# Lighting.net
KiCad netlist of a schematic drawn in Altium Designer
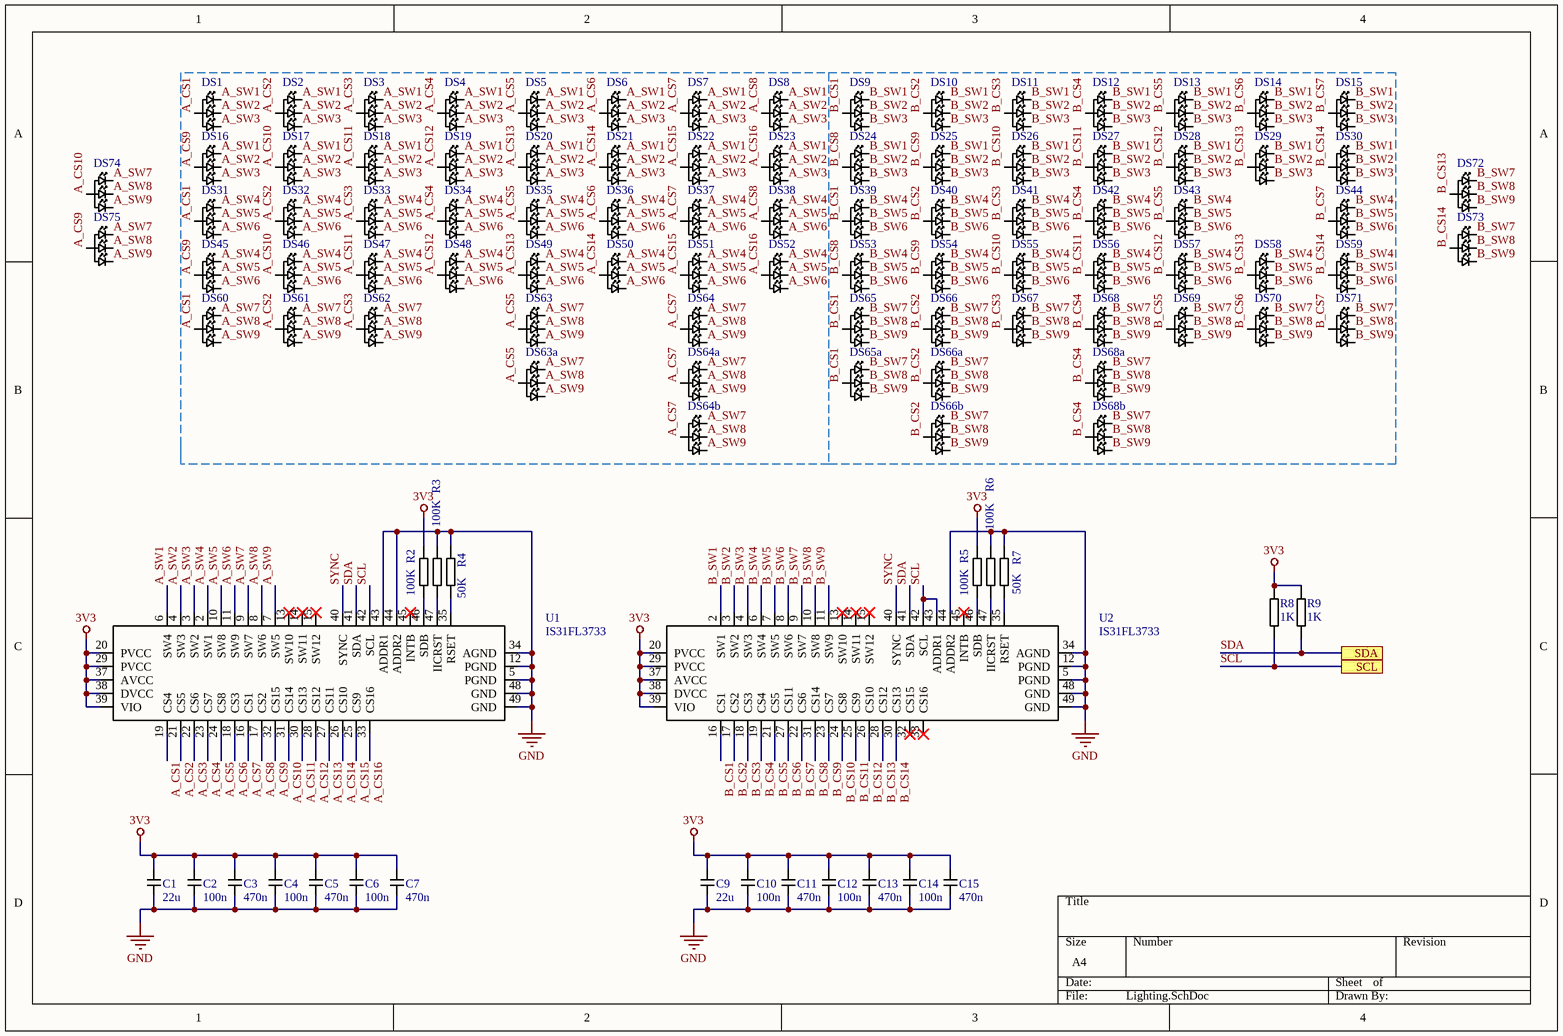
[diagram p0: Lighting.SchDoc]

(export (version "E")
  (design (tool "Eeschema 10.0.6"))
  (components
    (comp (ref "C1")
      (value "22u")
      (footprint "Capacitor_0603")
      (libsource (lib "NautilusKB") (part "Capacitor"))
    )
    (comp (ref "C2")
      (value "100n")
      (footprint "Capacitor_0603")
      (libsource (lib "NautilusKB") (part "Capacitor"))
    )
    (comp (ref "C3")
      (value "470n")
      (footprint "Capacitor_0603")
      (libsource (lib "NautilusKB") (part "Capacitor"))
    )
    (comp (ref "C4")
      (value "100n")
      (footprint "Capacitor_0603")
      (libsource (lib "NautilusKB") (part "Capacitor"))
    )
    (comp (ref "C5")
      (value "470n")
      (footprint "Capacitor_0603")
      (libsource (lib "NautilusKB") (part "Capacitor"))
    )
    (comp (ref "C6")
      (value "100n")
      (footprint "Capacitor_0603")
      (libsource (lib "NautilusKB") (part "Capacitor"))
    )
    (comp (ref "C7")
      (value "470n")
      (footprint "Capacitor_0603")
      (libsource (lib "NautilusKB") (part "Capacitor"))
    )
    (comp (ref "C9")
      (value "22u")
      (footprint "Capacitor_0603")
      (libsource (lib "NautilusKB") (part "Capacitor"))
    )
    (comp (ref "C10")
      (value "100n")
      (footprint "Capacitor_0603")
      (libsource (lib "NautilusKB") (part "Capacitor"))
    )
    (comp (ref "C11")
      (value "470n")
      (footprint "Capacitor_0603")
      (libsource (lib "NautilusKB") (part "Capacitor"))
    )
    (comp (ref "C12")
      (value "100n")
      (footprint "Capacitor_0603")
      (libsource (lib "NautilusKB") (part "Capacitor"))
    )
    (comp (ref "C13")
      (value "470n")
      (footprint "Capacitor_0603")
      (libsource (lib "NautilusKB") (part "Capacitor"))
    )
    (comp (ref "C14")
      (value "100n")
      (footprint "Capacitor_0603")
      (libsource (lib "NautilusKB") (part "Capacitor"))
    )
    (comp (ref "C15")
      (value "470n")
      (footprint "Capacitor_0603")
      (libsource (lib "NautilusKB") (part "Capacitor"))
    )
    (comp (ref "DS1")
      (value "RGB_CA")
      (footprint "LED_1616_4P")
      (libsource (lib "NautilusKB") (part "RGB_CA"))
    )
    (comp (ref "DS2")
      (value "RGB_CA")
      (footprint "LED_1616_4P")
      (libsource (lib "NautilusKB") (part "RGB_CA"))
    )
    (comp (ref "DS3")
      (value "RGB_CA")
      (footprint "LED_1616_4P")
      (libsource (lib "NautilusKB") (part "RGB_CA"))
    )
    (comp (ref "DS4")
      (value "RGB_CA")
      (footprint "LED_1616_4P")
      (libsource (lib "NautilusKB") (part "RGB_CA"))
    )
    (comp (ref "DS5")
      (value "RGB_CA")
      (footprint "LED_1616_4P")
      (libsource (lib "NautilusKB") (part "RGB_CA"))
    )
    (comp (ref "DS6")
      (value "RGB_CA")
      (footprint "LED_1616_4P")
      (libsource (lib "NautilusKB") (part "RGB_CA"))
    )
    (comp (ref "DS7")
      (value "RGB_CA")
      (footprint "LED_1616_4P")
      (libsource (lib "NautilusKB") (part "RGB_CA"))
    )
    (comp (ref "DS8")
      (value "RGB_CA")
      (footprint "LED_1616_4P")
      (libsource (lib "NautilusKB") (part "RGB_CA"))
    )
    (comp (ref "DS9")
      (value "RGB_CA")
      (footprint "LED_1616_4P")
      (libsource (lib "NautilusKB") (part "RGB_CA"))
    )
    (comp (ref "DS10")
      (value "RGB_CA")
      (footprint "LED_1616_4P")
      (libsource (lib "NautilusKB") (part "RGB_CA"))
    )
    (comp (ref "DS11")
      (value "RGB_CA")
      (footprint "LED_1616_4P")
      (libsource (lib "NautilusKB") (part "RGB_CA"))
    )
    (comp (ref "DS12")
      (value "RGB_CA")
      (footprint "LED_1616_4P")
      (libsource (lib "NautilusKB") (part "RGB_CA"))
    )
    (comp (ref "DS13")
      (value "RGB_CA")
      (footprint "LED_1616_4P")
      (libsource (lib "NautilusKB") (part "RGB_CA"))
    )
    (comp (ref "DS14")
      (value "RGB_CA")
      (footprint "LED_1616_4P")
      (libsource (lib "NautilusKB") (part "RGB_CA"))
    )
    (comp (ref "DS15")
      (value "RGB_CA")
      (footprint "LED_1616_4P")
      (libsource (lib "NautilusKB") (part "RGB_CA"))
    )
    (comp (ref "DS16")
      (value "RGB_CA")
      (footprint "LED_1616_4P")
      (libsource (lib "NautilusKB") (part "RGB_CA"))
    )
    (comp (ref "DS17")
      (value "RGB_CA")
      (footprint "LED_1616_4P")
      (libsource (lib "NautilusKB") (part "RGB_CA"))
    )
    (comp (ref "DS18")
      (value "RGB_CA")
      (footprint "LED_1616_4P")
      (libsource (lib "NautilusKB") (part "RGB_CA"))
    )
    (comp (ref "DS19")
      (value "RGB_CA")
      (footprint "LED_1616_4P")
      (libsource (lib "NautilusKB") (part "RGB_CA"))
    )
    (comp (ref "DS20")
      (value "RGB_CA")
      (footprint "LED_1616_4P")
      (libsource (lib "NautilusKB") (part "RGB_CA"))
    )
    (comp (ref "DS21")
      (value "RGB_CA")
      (footprint "LED_1616_4P")
      (libsource (lib "NautilusKB") (part "RGB_CA"))
    )
    (comp (ref "DS22")
      (value "RGB_CA")
      (footprint "LED_1616_4P")
      (libsource (lib "NautilusKB") (part "RGB_CA"))
    )
    (comp (ref "DS23")
      (value "RGB_CA")
      (footprint "LED_1616_4P")
      (libsource (lib "NautilusKB") (part "RGB_CA"))
    )
    (comp (ref "DS24")
      (value "RGB_CA")
      (footprint "LED_1616_4P")
      (libsource (lib "NautilusKB") (part "RGB_CA"))
    )
    (comp (ref "DS25")
      (value "RGB_CA")
      (footprint "LED_1616_4P")
      (libsource (lib "NautilusKB") (part "RGB_CA"))
    )
    (comp (ref "DS26")
      (value "RGB_CA")
      (footprint "LED_1616_4P")
      (libsource (lib "NautilusKB") (part "RGB_CA"))
    )
    (comp (ref "DS27")
      (value "RGB_CA")
      (footprint "LED_1616_4P")
      (libsource (lib "NautilusKB") (part "RGB_CA"))
    )
    (comp (ref "DS28")
      (value "RGB_CA")
      (footprint "LED_1616_4P")
      (libsource (lib "NautilusKB") (part "RGB_CA"))
    )
    (comp (ref "DS29")
      (value "RGB_CA")
      (footprint "LED_1616_4P")
      (libsource (lib "NautilusKB") (part "RGB_CA"))
    )
    (comp (ref "DS30")
      (value "RGB_CA")
      (footprint "LED_1616_4P")
      (libsource (lib "NautilusKB") (part "RGB_CA"))
    )
    (comp (ref "DS31")
      (value "RGB_CA")
      (footprint "LED_1616_4P")
      (libsource (lib "NautilusKB") (part "RGB_CA"))
    )
    (comp (ref "DS32")
      (value "RGB_CA")
      (footprint "LED_1616_4P")
      (libsource (lib "NautilusKB") (part "RGB_CA"))
    )
    (comp (ref "DS33")
      (value "RGB_CA")
      (footprint "LED_1616_4P")
      (libsource (lib "NautilusKB") (part "RGB_CA"))
    )
    (comp (ref "DS34")
      (value "RGB_CA")
      (footprint "LED_1616_4P")
      (libsource (lib "NautilusKB") (part "RGB_CA"))
    )
    (comp (ref "DS35")
      (value "RGB_CA")
      (footprint "LED_1616_4P")
      (libsource (lib "NautilusKB") (part "RGB_CA"))
    )
    (comp (ref "DS36")
      (value "RGB_CA")
      (footprint "LED_1616_4P")
      (libsource (lib "NautilusKB") (part "RGB_CA"))
    )
    (comp (ref "DS37")
      (value "RGB_CA")
      (footprint "LED_1616_4P")
      (libsource (lib "NautilusKB") (part "RGB_CA"))
    )
    (comp (ref "DS38")
      (value "RGB_CA")
      (footprint "LED_1616_4P")
      (libsource (lib "NautilusKB") (part "RGB_CA"))
    )
    (comp (ref "DS39")
      (value "RGB_CA")
      (footprint "LED_1616_4P")
      (libsource (lib "NautilusKB") (part "RGB_CA"))
    )
    (comp (ref "DS40")
      (value "RGB_CA")
      (footprint "LED_1616_4P")
      (libsource (lib "NautilusKB") (part "RGB_CA"))
    )
    (comp (ref "DS41")
      (value "RGB_CA")
      (footprint "LED_1616_4P")
      (libsource (lib "NautilusKB") (part "RGB_CA"))
    )
    (comp (ref "DS42")
      (value "RGB_CA")
      (footprint "LED_1616_4P")
      (libsource (lib "NautilusKB") (part "RGB_CA"))
    )
    (comp (ref "DS43")
      (value "RGB_CA")
      (footprint "LED_1616_4P")
      (libsource (lib "NautilusKB") (part "RGB_CA"))
    )
    (comp (ref "DS44")
      (value "RGB_CA")
      (footprint "LED_1616_4P")
      (libsource (lib "NautilusKB") (part "RGB_CA"))
    )
    (comp (ref "DS45")
      (value "RGB_CA")
      (footprint "LED_1616_4P")
      (libsource (lib "NautilusKB") (part "RGB_CA"))
    )
    (comp (ref "DS46")
      (value "RGB_CA")
      (footprint "LED_1616_4P")
      (libsource (lib "NautilusKB") (part "RGB_CA"))
    )
    (comp (ref "DS47")
      (value "RGB_CA")
      (footprint "LED_1616_4P")
      (libsource (lib "NautilusKB") (part "RGB_CA"))
    )
    (comp (ref "DS48")
      (value "RGB_CA")
      (footprint "LED_1616_4P")
      (libsource (lib "NautilusKB") (part "RGB_CA"))
    )
    (comp (ref "DS49")
      (value "RGB_CA")
      (footprint "LED_1616_4P")
      (libsource (lib "NautilusKB") (part "RGB_CA"))
    )
    (comp (ref "DS50")
      (value "RGB_CA")
      (footprint "LED_1616_4P")
      (libsource (lib "NautilusKB") (part "RGB_CA"))
    )
    (comp (ref "DS51")
      (value "RGB_CA")
      (footprint "LED_1616_4P")
      (libsource (lib "NautilusKB") (part "RGB_CA"))
    )
    (comp (ref "DS52")
      (value "RGB_CA")
      (footprint "LED_1616_4P")
      (libsource (lib "NautilusKB") (part "RGB_CA"))
    )
    (comp (ref "DS53")
      (value "RGB_CA")
      (footprint "LED_1616_4P")
      (libsource (lib "NautilusKB") (part "RGB_CA"))
    )
    (comp (ref "DS54")
      (value "RGB_CA")
      (footprint "LED_1616_4P")
      (libsource (lib "NautilusKB") (part "RGB_CA"))
    )
    (comp (ref "DS55")
      (value "RGB_CA")
      (footprint "LED_1616_4P")
      (libsource (lib "NautilusKB") (part "RGB_CA"))
    )
    (comp (ref "DS56")
      (value "RGB_CA")
      (footprint "LED_1616_4P")
      (libsource (lib "NautilusKB") (part "RGB_CA"))
    )
    (comp (ref "DS57")
      (value "RGB_CA")
      (footprint "LED_1616_4P")
      (libsource (lib "NautilusKB") (part "RGB_CA"))
    )
    (comp (ref "DS58")
      (value "RGB_CA")
      (footprint "LED_1616_4P")
      (libsource (lib "NautilusKB") (part "RGB_CA"))
    )
    (comp (ref "DS59")
      (value "RGB_CA")
      (footprint "LED_1616_4P")
      (libsource (lib "NautilusKB") (part "RGB_CA"))
    )
    (comp (ref "DS60")
      (value "RGB_CA")
      (footprint "LED_1616_4P")
      (libsource (lib "NautilusKB") (part "RGB_CA"))
    )
    (comp (ref "DS61")
      (value "RGB_CA")
      (footprint "LED_1616_4P")
      (libsource (lib "NautilusKB") (part "RGB_CA"))
    )
    (comp (ref "DS62")
      (value "RGB_CA")
      (footprint "LED_1616_4P")
      (libsource (lib "NautilusKB") (part "RGB_CA"))
    )
    (comp (ref "DS63")
      (value "RGB_CA")
      (footprint "LED_1616_4P")
      (libsource (lib "NautilusKB") (part "RGB_CA"))
    )
    (comp (ref "DS63a")
      (value "RGB_CA")
      (footprint "LED_1616_4P")
      (libsource (lib "NautilusKB") (part "RGB_CA"))
    )
    (comp (ref "DS64")
      (value "RGB_CA")
      (footprint "LED_1616_4P")
      (libsource (lib "NautilusKB") (part "RGB_CA"))
    )
    (comp (ref "DS64a")
      (value "RGB_CA")
      (footprint "LED_1616_4P")
      (libsource (lib "NautilusKB") (part "RGB_CA"))
    )
    (comp (ref "DS64b")
      (value "RGB_CA")
      (footprint "LED_1616_4P")
      (libsource (lib "NautilusKB") (part "RGB_CA"))
    )
    (comp (ref "DS65")
      (value "RGB_CA")
      (footprint "LED_1616_4P")
      (libsource (lib "NautilusKB") (part "RGB_CA"))
    )
    (comp (ref "DS65a")
      (value "RGB_CA")
      (footprint "LED_1616_4P")
      (libsource (lib "NautilusKB") (part "RGB_CA"))
    )
    (comp (ref "DS66")
      (value "RGB_CA")
      (footprint "LED_1616_4P")
      (libsource (lib "NautilusKB") (part "RGB_CA"))
    )
    (comp (ref "DS66a")
      (value "RGB_CA")
      (footprint "LED_1616_4P")
      (libsource (lib "NautilusKB") (part "RGB_CA"))
    )
    (comp (ref "DS66b")
      (value "RGB_CA")
      (footprint "LED_1616_4P")
      (libsource (lib "NautilusKB") (part "RGB_CA"))
    )
    (comp (ref "DS67")
      (value "RGB_CA")
      (footprint "LED_1616_4P")
      (libsource (lib "NautilusKB") (part "RGB_CA"))
    )
    (comp (ref "DS68")
      (value "RGB_CA")
      (footprint "LED_1616_4P")
      (libsource (lib "NautilusKB") (part "RGB_CA"))
    )
    (comp (ref "DS68a")
      (value "RGB_CA")
      (footprint "LED_1616_4P")
      (libsource (lib "NautilusKB") (part "RGB_CA"))
    )
    (comp (ref "DS68b")
      (value "RGB_CA")
      (footprint "LED_1616_4P")
      (libsource (lib "NautilusKB") (part "RGB_CA"))
    )
    (comp (ref "DS69")
      (value "RGB_CA")
      (footprint "LED_1616_4P")
      (libsource (lib "NautilusKB") (part "RGB_CA"))
    )
    (comp (ref "DS70")
      (value "RGB_CA")
      (footprint "LED_1616_4P")
      (libsource (lib "NautilusKB") (part "RGB_CA"))
    )
    (comp (ref "DS71")
      (value "RGB_CA")
      (footprint "LED_1616_4P")
      (libsource (lib "NautilusKB") (part "RGB_CA"))
    )
    (comp (ref "DS72")
      (value "RGB_CA")
      (footprint "LED_1616_4P")
      (libsource (lib "NautilusKB") (part "RGB_CA"))
    )
    (comp (ref "DS73")
      (value "RGB_CA")
      (footprint "LED_1616_4P")
      (libsource (lib "NautilusKB") (part "RGB_CA"))
    )
    (comp (ref "DS74")
      (value "RGB_CA")
      (footprint "LED_1616_4P")
      (libsource (lib "NautilusKB") (part "RGB_CA"))
    )
    (comp (ref "DS75")
      (value "RGB_CA")
      (footprint "LED_1616_4P")
      (libsource (lib "NautilusKB") (part "RGB_CA"))
    )
    (comp (ref "R2")
      (value "100K")
      (footprint "Resistor_0603")
      (libsource (lib "NautilusKB") (part "Resistor"))
    )
    (comp (ref "R3")
      (value "100K")
      (footprint "Resistor_0603")
      (libsource (lib "NautilusKB") (part "Resistor"))
    )
    (comp (ref "R4")
      (value "50K")
      (footprint "Resistor_0603")
      (libsource (lib "NautilusKB") (part "Resistor"))
    )
    (comp (ref "R5")
      (value "100K")
      (footprint "Resistor_0603")
      (libsource (lib "NautilusKB") (part "Resistor"))
    )
    (comp (ref "R6")
      (value "100K")
      (footprint "Resistor_0603")
      (libsource (lib "NautilusKB") (part "Resistor"))
    )
    (comp (ref "R7")
      (value "50K")
      (footprint "Resistor_0603")
      (libsource (lib "NautilusKB") (part "Resistor"))
    )
    (comp (ref "R8")
      (value "1K")
      (footprint "Resistor_0603")
      (libsource (lib "NautilusKB") (part "Resistor"))
    )
    (comp (ref "R9")
      (value "1K")
      (footprint "Resistor_0603")
      (libsource (lib "NautilusKB") (part "Resistor"))
    )
    (comp (ref "U1")
      (value "IS31FL3733")
      (footprint "QFP_48_7mm_TP")
      (libsource (lib "NautilusKB") (part "IS31FL3733"))
    )
    (comp (ref "U2")
      (value "IS31FL3733")
      (footprint "QFP_48_7mm_TP")
      (libsource (lib "") (part "IS31FL3733_1"))
    )
  )
  (nets
    (net (code "1") (name "/A_CS1") (class "Default")
      (node (ref "DS1") (pin "3") (pintype "passive"))
      (node (ref "DS31") (pin "3") (pintype "passive"))
      (node (ref "DS60") (pin "3") (pintype "passive"))
      (node (ref "U1") (pin "19") (pinfunction "CS4_19") (pintype "passive"))
    )
    (net (code "2") (name "/A_CS2") (class "Default")
      (node (ref "DS2") (pin "3") (pintype "passive"))
      (node (ref "DS32") (pin "3") (pintype "passive"))
      (node (ref "DS61") (pin "3") (pintype "passive"))
      (node (ref "U1") (pin "21") (pinfunction "CS5_21") (pintype "passive"))
    )
    (net (code "3") (name "/A_CS3") (class "Default")
      (node (ref "DS3") (pin "3") (pintype "passive"))
      (node (ref "DS33") (pin "3") (pintype "passive"))
      (node (ref "DS62") (pin "3") (pintype "passive"))
      (node (ref "U1") (pin "22") (pinfunction "CS6_22") (pintype "passive"))
    )
    (net (code "4") (name "/A_CS4") (class "Default")
      (node (ref "DS34") (pin "3") (pintype "passive"))
      (node (ref "DS4") (pin "3") (pintype "passive"))
      (node (ref "U1") (pin "23") (pinfunction "CS7_23") (pintype "passive"))
    )
    (net (code "5") (name "/A_CS5") (class "Default")
      (node (ref "DS35") (pin "3") (pintype "passive"))
      (node (ref "DS5") (pin "3") (pintype "passive"))
      (node (ref "DS63") (pin "3") (pintype "passive"))
      (node (ref "DS63a") (pin "3") (pintype "passive"))
      (node (ref "U1") (pin "24") (pinfunction "CS8_24") (pintype "passive"))
    )
    (net (code "6") (name "/A_CS6") (class "Default")
      (node (ref "DS36") (pin "3") (pintype "passive"))
      (node (ref "DS6") (pin "3") (pintype "passive"))
      (node (ref "U1") (pin "18") (pinfunction "CS3_18") (pintype "passive"))
    )
    (net (code "7") (name "/A_CS7") (class "Default")
      (node (ref "DS37") (pin "3") (pintype "passive"))
      (node (ref "DS64") (pin "3") (pintype "passive"))
      (node (ref "DS64a") (pin "3") (pintype "passive"))
      (node (ref "DS64b") (pin "3") (pintype "passive"))
      (node (ref "DS7") (pin "3") (pintype "passive"))
      (node (ref "U1") (pin "16") (pinfunction "CS1_16") (pintype "passive"))
    )
    (net (code "8") (name "/A_CS8") (class "Default")
      (node (ref "DS38") (pin "3") (pintype "passive"))
      (node (ref "DS8") (pin "3") (pintype "passive"))
      (node (ref "U1") (pin "17") (pinfunction "CS2_17") (pintype "passive"))
    )
    (net (code "9") (name "/A_CS9") (class "Default")
      (node (ref "DS16") (pin "3") (pintype "passive"))
      (node (ref "DS45") (pin "3") (pintype "passive"))
      (node (ref "DS75") (pin "3") (pintype "passive"))
      (node (ref "U1") (pin "32") (pinfunction "CS15_32") (pintype "passive"))
    )
    (net (code "10") (name "/A_CS10") (class "Default")
      (node (ref "DS17") (pin "3") (pintype "passive"))
      (node (ref "DS46") (pin "3") (pintype "passive"))
      (node (ref "DS74") (pin "3") (pintype "passive"))
      (node (ref "U1") (pin "31") (pinfunction "CS14_31") (pintype "passive"))
    )
    (net (code "11") (name "/A_CS11") (class "Default")
      (node (ref "DS18") (pin "3") (pintype "passive"))
      (node (ref "DS47") (pin "3") (pintype "passive"))
      (node (ref "U1") (pin "30") (pinfunction "CS13_30") (pintype "passive"))
    )
    (net (code "12") (name "/A_CS12") (class "Default")
      (node (ref "DS19") (pin "3") (pintype "passive"))
      (node (ref "DS48") (pin "3") (pintype "passive"))
      (node (ref "U1") (pin "28") (pinfunction "CS12_28") (pintype "passive"))
    )
    (net (code "13") (name "/A_CS13") (class "Default")
      (node (ref "DS20") (pin "3") (pintype "passive"))
      (node (ref "DS49") (pin "3") (pintype "passive"))
      (node (ref "U1") (pin "27") (pinfunction "CS11_27") (pintype "passive"))
    )
    (net (code "14") (name "/A_CS14") (class "Default")
      (node (ref "DS21") (pin "3") (pintype "passive"))
      (node (ref "DS50") (pin "3") (pintype "passive"))
      (node (ref "U1") (pin "26") (pinfunction "CS10_26") (pintype "passive"))
    )
    (net (code "15") (name "/A_CS15") (class "Default")
      (node (ref "DS22") (pin "3") (pintype "passive"))
      (node (ref "DS51") (pin "3") (pintype "passive"))
      (node (ref "U1") (pin "25") (pinfunction "CS9_25") (pintype "passive"))
    )
    (net (code "16") (name "/A_CS16") (class "Default")
      (node (ref "DS23") (pin "3") (pintype "passive"))
      (node (ref "DS52") (pin "3") (pintype "passive"))
      (node (ref "U1") (pin "33") (pinfunction "CS16_33") (pintype "passive"))
    )
    (net (code "17") (name "/A_SW1") (class "Default")
      (node (ref "DS1") (pin "1") (pintype "passive"))
      (node (ref "DS16") (pin "1") (pintype "passive"))
      (node (ref "DS17") (pin "1") (pintype "passive"))
      (node (ref "DS18") (pin "1") (pintype "passive"))
      (node (ref "DS19") (pin "1") (pintype "passive"))
      (node (ref "DS2") (pin "1") (pintype "passive"))
      (node (ref "DS20") (pin "1") (pintype "passive"))
      (node (ref "DS21") (pin "1") (pintype "passive"))
      (node (ref "DS22") (pin "1") (pintype "passive"))
      (node (ref "DS23") (pin "1") (pintype "passive"))
      (node (ref "DS3") (pin "1") (pintype "passive"))
      (node (ref "DS4") (pin "1") (pintype "passive"))
      (node (ref "DS5") (pin "1") (pintype "passive"))
      (node (ref "DS6") (pin "1") (pintype "passive"))
      (node (ref "DS7") (pin "1") (pintype "passive"))
      (node (ref "DS8") (pin "1") (pintype "passive"))
      (node (ref "U1") (pin "6") (pinfunction "SW4_6") (pintype "passive"))
    )
    (net (code "18") (name "/A_SW2") (class "Default")
      (node (ref "DS1") (pin "2") (pintype "passive"))
      (node (ref "DS16") (pin "2") (pintype "passive"))
      (node (ref "DS17") (pin "2") (pintype "passive"))
      (node (ref "DS18") (pin "2") (pintype "passive"))
      (node (ref "DS19") (pin "2") (pintype "passive"))
      (node (ref "DS2") (pin "2") (pintype "passive"))
      (node (ref "DS20") (pin "2") (pintype "passive"))
      (node (ref "DS21") (pin "2") (pintype "passive"))
      (node (ref "DS22") (pin "2") (pintype "passive"))
      (node (ref "DS23") (pin "2") (pintype "passive"))
      (node (ref "DS3") (pin "2") (pintype "passive"))
      (node (ref "DS4") (pin "2") (pintype "passive"))
      (node (ref "DS5") (pin "2") (pintype "passive"))
      (node (ref "DS6") (pin "2") (pintype "passive"))
      (node (ref "DS7") (pin "2") (pintype "passive"))
      (node (ref "DS8") (pin "2") (pintype "passive"))
      (node (ref "U1") (pin "4") (pinfunction "SW3_4") (pintype "passive"))
    )
    (net (code "19") (name "/A_SW3") (class "Default")
      (node (ref "DS1") (pin "4") (pintype "passive"))
      (node (ref "DS16") (pin "4") (pintype "passive"))
      (node (ref "DS17") (pin "4") (pintype "passive"))
      (node (ref "DS18") (pin "4") (pintype "passive"))
      (node (ref "DS19") (pin "4") (pintype "passive"))
      (node (ref "DS2") (pin "4") (pintype "passive"))
      (node (ref "DS20") (pin "4") (pintype "passive"))
      (node (ref "DS21") (pin "4") (pintype "passive"))
      (node (ref "DS22") (pin "4") (pintype "passive"))
      (node (ref "DS23") (pin "4") (pintype "passive"))
      (node (ref "DS3") (pin "4") (pintype "passive"))
      (node (ref "DS4") (pin "4") (pintype "passive"))
      (node (ref "DS5") (pin "4") (pintype "passive"))
      (node (ref "DS6") (pin "4") (pintype "passive"))
      (node (ref "DS7") (pin "4") (pintype "passive"))
      (node (ref "DS8") (pin "4") (pintype "passive"))
      (node (ref "U1") (pin "3") (pinfunction "SW2_3") (pintype "passive"))
    )
    (net (code "20") (name "/A_SW4") (class "Default")
      (node (ref "DS31") (pin "1") (pintype "passive"))
      (node (ref "DS32") (pin "1") (pintype "passive"))
      (node (ref "DS33") (pin "1") (pintype "passive"))
      (node (ref "DS34") (pin "1") (pintype "passive"))
      (node (ref "DS35") (pin "1") (pintype "passive"))
      (node (ref "DS36") (pin "1") (pintype "passive"))
      (node (ref "DS37") (pin "1") (pintype "passive"))
      (node (ref "DS38") (pin "1") (pintype "passive"))
      (node (ref "DS45") (pin "1") (pintype "passive"))
      (node (ref "DS46") (pin "1") (pintype "passive"))
      (node (ref "DS47") (pin "1") (pintype "passive"))
      (node (ref "DS48") (pin "1") (pintype "passive"))
      (node (ref "DS49") (pin "1") (pintype "passive"))
      (node (ref "DS50") (pin "1") (pintype "passive"))
      (node (ref "DS51") (pin "1") (pintype "passive"))
      (node (ref "DS52") (pin "1") (pintype "passive"))
      (node (ref "U1") (pin "2") (pinfunction "SW1_2") (pintype "passive"))
    )
    (net (code "21") (name "/A_SW5") (class "Default")
      (node (ref "DS31") (pin "2") (pintype "passive"))
      (node (ref "DS32") (pin "2") (pintype "passive"))
      (node (ref "DS33") (pin "2") (pintype "passive"))
      (node (ref "DS34") (pin "2") (pintype "passive"))
      (node (ref "DS35") (pin "2") (pintype "passive"))
      (node (ref "DS36") (pin "2") (pintype "passive"))
      (node (ref "DS37") (pin "2") (pintype "passive"))
      (node (ref "DS38") (pin "2") (pintype "passive"))
      (node (ref "DS45") (pin "2") (pintype "passive"))
      (node (ref "DS46") (pin "2") (pintype "passive"))
      (node (ref "DS47") (pin "2") (pintype "passive"))
      (node (ref "DS48") (pin "2") (pintype "passive"))
      (node (ref "DS49") (pin "2") (pintype "passive"))
      (node (ref "DS50") (pin "2") (pintype "passive"))
      (node (ref "DS51") (pin "2") (pintype "passive"))
      (node (ref "DS52") (pin "2") (pintype "passive"))
      (node (ref "U1") (pin "10") (pinfunction "SW8_10") (pintype "passive"))
    )
    (net (code "22") (name "/A_SW6") (class "Default")
      (node (ref "DS31") (pin "4") (pintype "passive"))
      (node (ref "DS32") (pin "4") (pintype "passive"))
      (node (ref "DS33") (pin "4") (pintype "passive"))
      (node (ref "DS34") (pin "4") (pintype "passive"))
      (node (ref "DS35") (pin "4") (pintype "passive"))
      (node (ref "DS36") (pin "4") (pintype "passive"))
      (node (ref "DS37") (pin "4") (pintype "passive"))
      (node (ref "DS38") (pin "4") (pintype "passive"))
      (node (ref "DS45") (pin "4") (pintype "passive"))
      (node (ref "DS46") (pin "4") (pintype "passive"))
      (node (ref "DS47") (pin "4") (pintype "passive"))
      (node (ref "DS48") (pin "4") (pintype "passive"))
      (node (ref "DS49") (pin "4") (pintype "passive"))
      (node (ref "DS50") (pin "4") (pintype "passive"))
      (node (ref "DS51") (pin "4") (pintype "passive"))
      (node (ref "DS52") (pin "4") (pintype "passive"))
      (node (ref "U1") (pin "11") (pinfunction "SW9_11") (pintype "passive"))
    )
    (net (code "23") (name "/A_SW7") (class "Default")
      (node (ref "DS60") (pin "1") (pintype "passive"))
      (node (ref "DS61") (pin "1") (pintype "passive"))
      (node (ref "DS62") (pin "1") (pintype "passive"))
      (node (ref "DS63") (pin "1") (pintype "passive"))
      (node (ref "DS63a") (pin "1") (pintype "passive"))
      (node (ref "DS64") (pin "1") (pintype "passive"))
      (node (ref "DS64a") (pin "1") (pintype "passive"))
      (node (ref "DS64b") (pin "1") (pintype "passive"))
      (node (ref "DS74") (pin "1") (pintype "passive"))
      (node (ref "DS75") (pin "1") (pintype "passive"))
      (node (ref "U1") (pin "9") (pinfunction "SW7_9") (pintype "passive"))
    )
    (net (code "24") (name "/A_SW8") (class "Default")
      (node (ref "DS60") (pin "2") (pintype "passive"))
      (node (ref "DS61") (pin "2") (pintype "passive"))
      (node (ref "DS62") (pin "2") (pintype "passive"))
      (node (ref "DS63") (pin "2") (pintype "passive"))
      (node (ref "DS63a") (pin "2") (pintype "passive"))
      (node (ref "DS64") (pin "2") (pintype "passive"))
      (node (ref "DS64a") (pin "2") (pintype "passive"))
      (node (ref "DS64b") (pin "2") (pintype "passive"))
      (node (ref "DS74") (pin "2") (pintype "passive"))
      (node (ref "DS75") (pin "2") (pintype "passive"))
      (node (ref "U1") (pin "8") (pinfunction "SW6_8") (pintype "passive"))
    )
    (net (code "25") (name "/A_SW9") (class "Default")
      (node (ref "DS60") (pin "4") (pintype "passive"))
      (node (ref "DS61") (pin "4") (pintype "passive"))
      (node (ref "DS62") (pin "4") (pintype "passive"))
      (node (ref "DS63") (pin "4") (pintype "passive"))
      (node (ref "DS63a") (pin "4") (pintype "passive"))
      (node (ref "DS64") (pin "4") (pintype "passive"))
      (node (ref "DS64a") (pin "4") (pintype "passive"))
      (node (ref "DS64b") (pin "4") (pintype "passive"))
      (node (ref "DS74") (pin "4") (pintype "passive"))
      (node (ref "DS75") (pin "4") (pintype "passive"))
      (node (ref "U1") (pin "7") (pinfunction "SW5_7") (pintype "passive"))
    )
    (net (code "26") (name "/B_CS1") (class "Default")
      (node (ref "DS39") (pin "3") (pintype "passive"))
      (node (ref "DS65") (pin "3") (pintype "passive"))
      (node (ref "DS65a") (pin "3") (pintype "passive"))
      (node (ref "DS9") (pin "3") (pintype "passive"))
      (node (ref "U2") (pin "16") (pinfunction "CS1_16") (pintype "passive"))
    )
    (net (code "27") (name "/B_CS2") (class "Default")
      (node (ref "DS10") (pin "3") (pintype "passive"))
      (node (ref "DS40") (pin "3") (pintype "passive"))
      (node (ref "DS66") (pin "3") (pintype "passive"))
      (node (ref "DS66a") (pin "3") (pintype "passive"))
      (node (ref "DS66b") (pin "3") (pintype "passive"))
      (node (ref "U2") (pin "17") (pinfunction "CS2_17") (pintype "passive"))
    )
    (net (code "28") (name "/B_CS3") (class "Default")
      (node (ref "DS11") (pin "3") (pintype "passive"))
      (node (ref "DS41") (pin "3") (pintype "passive"))
      (node (ref "DS67") (pin "3") (pintype "passive"))
      (node (ref "U2") (pin "18") (pinfunction "CS3_18") (pintype "passive"))
    )
    (net (code "29") (name "/B_CS4") (class "Default")
      (node (ref "DS12") (pin "3") (pintype "passive"))
      (node (ref "DS42") (pin "3") (pintype "passive"))
      (node (ref "DS68") (pin "3") (pintype "passive"))
      (node (ref "DS68a") (pin "3") (pintype "passive"))
      (node (ref "DS68b") (pin "3") (pintype "passive"))
      (node (ref "U2") (pin "19") (pinfunction "CS4_19") (pintype "passive"))
    )
    (net (code "30") (name "/B_CS5") (class "Default")
      (node (ref "DS13") (pin "3") (pintype "passive"))
      (node (ref "DS43") (pin "3") (pintype "passive"))
      (node (ref "DS69") (pin "3") (pintype "passive"))
      (node (ref "U2") (pin "21") (pinfunction "CS5_21") (pintype "passive"))
    )
    (net (code "31") (name "/B_CS6") (class "Default")
      (node (ref "DS14") (pin "3") (pintype "passive"))
      (node (ref "DS70") (pin "3") (pintype "passive"))
      (node (ref "U2") (pin "27") (pinfunction "CS11_27") (pintype "passive"))
    )
    (net (code "32") (name "/B_CS7") (class "Default")
      (node (ref "DS15") (pin "3") (pintype "passive"))
      (node (ref "DS44") (pin "3") (pintype "passive"))
      (node (ref "DS71") (pin "3") (pintype "passive"))
      (node (ref "U2") (pin "22") (pinfunction "CS6_22") (pintype "passive"))
    )
    (net (code "33") (name "/B_CS8") (class "Default")
      (node (ref "DS24") (pin "3") (pintype "passive"))
      (node (ref "DS53") (pin "3") (pintype "passive"))
      (node (ref "U2") (pin "31") (pinfunction "CS14_31") (pintype "passive"))
    )
    (net (code "34") (name "/B_CS9") (class "Default")
      (node (ref "DS25") (pin "3") (pintype "passive"))
      (node (ref "DS54") (pin "3") (pintype "passive"))
      (node (ref "U2") (pin "23") (pinfunction "CS7_23") (pintype "passive"))
    )
    (net (code "35") (name "/B_CS10") (class "Default")
      (node (ref "DS26") (pin "3") (pintype "passive"))
      (node (ref "DS55") (pin "3") (pintype "passive"))
      (node (ref "U2") (pin "24") (pinfunction "CS8_24") (pintype "passive"))
    )
    (net (code "36") (name "/B_CS11") (class "Default")
      (node (ref "DS27") (pin "3") (pintype "passive"))
      (node (ref "DS56") (pin "3") (pintype "passive"))
      (node (ref "U2") (pin "25") (pinfunction "CS9_25") (pintype "passive"))
    )
    (net (code "37") (name "/B_CS12") (class "Default")
      (node (ref "DS28") (pin "3") (pintype "passive"))
      (node (ref "DS57") (pin "3") (pintype "passive"))
      (node (ref "U2") (pin "26") (pinfunction "CS10_26") (pintype "passive"))
    )
    (net (code "38") (name "/B_CS13") (class "Default")
      (node (ref "DS29") (pin "3") (pintype "passive"))
      (node (ref "DS58") (pin "3") (pintype "passive"))
      (node (ref "DS72") (pin "3") (pintype "passive"))
      (node (ref "U2") (pin "28") (pinfunction "CS12_28") (pintype "passive"))
    )
    (net (code "39") (name "/B_CS14") (class "Default")
      (node (ref "DS30") (pin "3") (pintype "passive"))
      (node (ref "DS59") (pin "3") (pintype "passive"))
      (node (ref "DS73") (pin "3") (pintype "passive"))
      (node (ref "U2") (pin "30") (pinfunction "CS13_30") (pintype "passive"))
    )
    (net (code "40") (name "/B_SW1") (class "Default")
      (node (ref "DS10") (pin "1") (pintype "passive"))
      (node (ref "DS11") (pin "1") (pintype "passive"))
      (node (ref "DS12") (pin "1") (pintype "passive"))
      (node (ref "DS13") (pin "1") (pintype "passive"))
      (node (ref "DS14") (pin "1") (pintype "passive"))
      (node (ref "DS15") (pin "1") (pintype "passive"))
      (node (ref "DS24") (pin "1") (pintype "passive"))
      (node (ref "DS25") (pin "1") (pintype "passive"))
      (node (ref "DS26") (pin "1") (pintype "passive"))
      (node (ref "DS27") (pin "1") (pintype "passive"))
      (node (ref "DS28") (pin "1") (pintype "passive"))
      (node (ref "DS29") (pin "1") (pintype "passive"))
      (node (ref "DS30") (pin "1") (pintype "passive"))
      (node (ref "DS9") (pin "1") (pintype "passive"))
      (node (ref "U2") (pin "2") (pinfunction "SW1_2") (pintype "passive"))
    )
    (net (code "41") (name "/B_SW2") (class "Default")
      (node (ref "DS10") (pin "2") (pintype "passive"))
      (node (ref "DS11") (pin "2") (pintype "passive"))
      (node (ref "DS12") (pin "2") (pintype "passive"))
      (node (ref "DS13") (pin "2") (pintype "passive"))
      (node (ref "DS14") (pin "2") (pintype "passive"))
      (node (ref "DS15") (pin "2") (pintype "passive"))
      (node (ref "DS24") (pin "2") (pintype "passive"))
      (node (ref "DS25") (pin "2") (pintype "passive"))
      (node (ref "DS26") (pin "2") (pintype "passive"))
      (node (ref "DS27") (pin "2") (pintype "passive"))
      (node (ref "DS28") (pin "2") (pintype "passive"))
      (node (ref "DS29") (pin "2") (pintype "passive"))
      (node (ref "DS30") (pin "2") (pintype "passive"))
      (node (ref "DS9") (pin "2") (pintype "passive"))
      (node (ref "U2") (pin "3") (pinfunction "SW2_3") (pintype "passive"))
    )
    (net (code "42") (name "/B_SW3") (class "Default")
      (node (ref "DS10") (pin "4") (pintype "passive"))
      (node (ref "DS11") (pin "4") (pintype "passive"))
      (node (ref "DS12") (pin "4") (pintype "passive"))
      (node (ref "DS13") (pin "4") (pintype "passive"))
      (node (ref "DS14") (pin "4") (pintype "passive"))
      (node (ref "DS15") (pin "4") (pintype "passive"))
      (node (ref "DS24") (pin "4") (pintype "passive"))
      (node (ref "DS25") (pin "4") (pintype "passive"))
      (node (ref "DS26") (pin "4") (pintype "passive"))
      (node (ref "DS27") (pin "4") (pintype "passive"))
      (node (ref "DS28") (pin "4") (pintype "passive"))
      (node (ref "DS29") (pin "4") (pintype "passive"))
      (node (ref "DS30") (pin "4") (pintype "passive"))
      (node (ref "DS9") (pin "4") (pintype "passive"))
      (node (ref "U2") (pin "4") (pinfunction "SW3_4") (pintype "passive"))
    )
    (net (code "43") (name "/B_SW4") (class "Default")
      (node (ref "DS39") (pin "1") (pintype "passive"))
      (node (ref "DS40") (pin "1") (pintype "passive"))
      (node (ref "DS41") (pin "1") (pintype "passive"))
      (node (ref "DS42") (pin "1") (pintype "passive"))
      (node (ref "DS43") (pin "1") (pintype "passive"))
      (node (ref "DS44") (pin "1") (pintype "passive"))
      (node (ref "DS53") (pin "1") (pintype "passive"))
      (node (ref "DS54") (pin "1") (pintype "passive"))
      (node (ref "DS55") (pin "1") (pintype "passive"))
      (node (ref "DS56") (pin "1") (pintype "passive"))
      (node (ref "DS57") (pin "1") (pintype "passive"))
      (node (ref "DS58") (pin "1") (pintype "passive"))
      (node (ref "DS59") (pin "1") (pintype "passive"))
      (node (ref "U2") (pin "6") (pinfunction "SW4_6") (pintype "passive"))
    )
    (net (code "44") (name "/B_SW5") (class "Default")
      (node (ref "DS39") (pin "2") (pintype "passive"))
      (node (ref "DS40") (pin "2") (pintype "passive"))
      (node (ref "DS41") (pin "2") (pintype "passive"))
      (node (ref "DS42") (pin "2") (pintype "passive"))
      (node (ref "DS43") (pin "2") (pintype "passive"))
      (node (ref "DS44") (pin "2") (pintype "passive"))
      (node (ref "DS53") (pin "2") (pintype "passive"))
      (node (ref "DS54") (pin "2") (pintype "passive"))
      (node (ref "DS55") (pin "2") (pintype "passive"))
      (node (ref "DS56") (pin "2") (pintype "passive"))
      (node (ref "DS57") (pin "2") (pintype "passive"))
      (node (ref "DS58") (pin "2") (pintype "passive"))
      (node (ref "DS59") (pin "2") (pintype "passive"))
      (node (ref "U2") (pin "7") (pinfunction "SW5_7") (pintype "passive"))
    )
    (net (code "45") (name "/B_SW6") (class "Default")
      (node (ref "DS39") (pin "4") (pintype "passive"))
      (node (ref "DS40") (pin "4") (pintype "passive"))
      (node (ref "DS41") (pin "4") (pintype "passive"))
      (node (ref "DS42") (pin "4") (pintype "passive"))
      (node (ref "DS43") (pin "4") (pintype "passive"))
      (node (ref "DS44") (pin "4") (pintype "passive"))
      (node (ref "DS53") (pin "4") (pintype "passive"))
      (node (ref "DS54") (pin "4") (pintype "passive"))
      (node (ref "DS55") (pin "4") (pintype "passive"))
      (node (ref "DS56") (pin "4") (pintype "passive"))
      (node (ref "DS57") (pin "4") (pintype "passive"))
      (node (ref "DS58") (pin "4") (pintype "passive"))
      (node (ref "DS59") (pin "4") (pintype "passive"))
      (node (ref "U2") (pin "8") (pinfunction "SW6_8") (pintype "passive"))
    )
    (net (code "46") (name "/B_SW7") (class "Default")
      (node (ref "DS65") (pin "1") (pintype "passive"))
      (node (ref "DS65a") (pin "1") (pintype "passive"))
      (node (ref "DS66") (pin "1") (pintype "passive"))
      (node (ref "DS66a") (pin "1") (pintype "passive"))
      (node (ref "DS66b") (pin "1") (pintype "passive"))
      (node (ref "DS67") (pin "1") (pintype "passive"))
      (node (ref "DS68") (pin "1") (pintype "passive"))
      (node (ref "DS68a") (pin "1") (pintype "passive"))
      (node (ref "DS68b") (pin "1") (pintype "passive"))
      (node (ref "DS69") (pin "1") (pintype "passive"))
      (node (ref "DS70") (pin "1") (pintype "passive"))
      (node (ref "DS71") (pin "1") (pintype "passive"))
      (node (ref "DS72") (pin "1") (pintype "passive"))
      (node (ref "DS73") (pin "1") (pintype "passive"))
      (node (ref "U2") (pin "9") (pinfunction "SW7_9") (pintype "passive"))
    )
    (net (code "47") (name "/B_SW8") (class "Default")
      (node (ref "DS65") (pin "2") (pintype "passive"))
      (node (ref "DS65a") (pin "2") (pintype "passive"))
      (node (ref "DS66") (pin "2") (pintype "passive"))
      (node (ref "DS66a") (pin "2") (pintype "passive"))
      (node (ref "DS66b") (pin "2") (pintype "passive"))
      (node (ref "DS67") (pin "2") (pintype "passive"))
      (node (ref "DS68") (pin "2") (pintype "passive"))
      (node (ref "DS68a") (pin "2") (pintype "passive"))
      (node (ref "DS68b") (pin "2") (pintype "passive"))
      (node (ref "DS69") (pin "2") (pintype "passive"))
      (node (ref "DS70") (pin "2") (pintype "passive"))
      (node (ref "DS71") (pin "2") (pintype "passive"))
      (node (ref "DS72") (pin "2") (pintype "passive"))
      (node (ref "DS73") (pin "2") (pintype "passive"))
      (node (ref "U2") (pin "10") (pinfunction "SW8_10") (pintype "passive"))
    )
    (net (code "48") (name "/B_SW9") (class "Default")
      (node (ref "DS65") (pin "4") (pintype "passive"))
      (node (ref "DS65a") (pin "4") (pintype "passive"))
      (node (ref "DS66") (pin "4") (pintype "passive"))
      (node (ref "DS66a") (pin "4") (pintype "passive"))
      (node (ref "DS66b") (pin "4") (pintype "passive"))
      (node (ref "DS67") (pin "4") (pintype "passive"))
      (node (ref "DS68") (pin "4") (pintype "passive"))
      (node (ref "DS68a") (pin "4") (pintype "passive"))
      (node (ref "DS68b") (pin "4") (pintype "passive"))
      (node (ref "DS69") (pin "4") (pintype "passive"))
      (node (ref "DS70") (pin "4") (pintype "passive"))
      (node (ref "DS71") (pin "4") (pintype "passive"))
      (node (ref "DS72") (pin "4") (pintype "passive"))
      (node (ref "DS73") (pin "4") (pintype "passive"))
      (node (ref "U2") (pin "11") (pinfunction "SW9_11") (pintype "passive"))
    )
    (net (code "49") (name "/SCL") (class "Default")
      (node (ref "R8") (pin "1") (pintype "passive"))
      (node (ref "U1") (pin "42") (pinfunction "SCL_42") (pintype "passive"))
      (node (ref "U2") (pin "42") (pinfunction "SCL_42") (pintype "passive"))
      (node (ref "U2") (pin "43") (pinfunction "ADDR1_43") (pintype "passive"))
    )
    (net (code "50") (name "/SDA") (class "Default")
      (node (ref "R9") (pin "1") (pintype "passive"))
      (node (ref "U1") (pin "41") (pinfunction "SDA_41") (pintype "passive"))
      (node (ref "U2") (pin "41") (pinfunction "SDA_41") (pintype "passive"))
    )
    (net (code "51") (name "/SYNC") (class "Default")
      (node (ref "U1") (pin "40") (pinfunction "SYNC_40") (pintype "passive"))
      (node (ref "U2") (pin "40") (pinfunction "SYNC_40") (pintype "passive"))
    )
    (net (code "52") (name "3V3") (class "Default")
      (node (ref "C1") (pin "2") (pintype "passive"))
      (node (ref "C10") (pin "2") (pintype "passive"))
      (node (ref "C11") (pin "2") (pintype "passive"))
      (node (ref "C12") (pin "2") (pintype "passive"))
      (node (ref "C13") (pin "2") (pintype "passive"))
      (node (ref "C14") (pin "2") (pintype "passive"))
      (node (ref "C15") (pin "2") (pintype "passive"))
      (node (ref "C2") (pin "2") (pintype "passive"))
      (node (ref "C3") (pin "2") (pintype "passive"))
      (node (ref "C4") (pin "2") (pintype "passive"))
      (node (ref "C5") (pin "2") (pintype "passive"))
      (node (ref "C6") (pin "2") (pintype "passive"))
      (node (ref "C7") (pin "2") (pintype "passive"))
      (node (ref "C9") (pin "2") (pintype "passive"))
      (node (ref "R2") (pin "2") (pintype "passive"))
      (node (ref "R5") (pin "2") (pintype "passive"))
      (node (ref "R8") (pin "2") (pintype "passive"))
      (node (ref "R9") (pin "2") (pintype "passive"))
      (node (ref "U1") (pin "20") (pinfunction "PVCC_20") (pintype "passive"))
      (node (ref "U1") (pin "29") (pinfunction "PVCC_29") (pintype "passive"))
      (node (ref "U1") (pin "37") (pinfunction "AVCC_37") (pintype "passive"))
      (node (ref "U1") (pin "38") (pinfunction "DVCC_38") (pintype "passive"))
      (node (ref "U1") (pin "39") (pinfunction "VIO_39") (pintype "passive"))
      (node (ref "U2") (pin "20") (pinfunction "PVCC_20") (pintype "passive"))
      (node (ref "U2") (pin "29") (pinfunction "PVCC_29") (pintype "passive"))
      (node (ref "U2") (pin "37") (pinfunction "AVCC_37") (pintype "passive"))
      (node (ref "U2") (pin "38") (pinfunction "DVCC_38") (pintype "passive"))
      (node (ref "U2") (pin "39") (pinfunction "VIO_39") (pintype "passive"))
    )
    (net (code "53") (name "GND") (class "Default")
      (node (ref "C1") (pin "1") (pintype "passive"))
      (node (ref "C10") (pin "1") (pintype "passive"))
      (node (ref "C11") (pin "1") (pintype "passive"))
      (node (ref "C12") (pin "1") (pintype "passive"))
      (node (ref "C13") (pin "1") (pintype "passive"))
      (node (ref "C14") (pin "1") (pintype "passive"))
      (node (ref "C15") (pin "1") (pintype "passive"))
      (node (ref "C2") (pin "1") (pintype "passive"))
      (node (ref "C3") (pin "1") (pintype "passive"))
      (node (ref "C4") (pin "1") (pintype "passive"))
      (node (ref "C5") (pin "1") (pintype "passive"))
      (node (ref "C6") (pin "1") (pintype "passive"))
      (node (ref "C7") (pin "1") (pintype "passive"))
      (node (ref "C9") (pin "1") (pintype "passive"))
      (node (ref "R3") (pin "2") (pintype "passive"))
      (node (ref "R4") (pin "2") (pintype "passive"))
      (node (ref "R6") (pin "2") (pintype "passive"))
      (node (ref "R7") (pin "2") (pintype "passive"))
      (node (ref "U1") (pin "12") (pinfunction "PGND_12") (pintype "passive"))
      (node (ref "U1") (pin "34") (pinfunction "AGND_34") (pintype "passive"))
      (node (ref "U1") (pin "43") (pinfunction "ADDR1_43") (pintype "passive"))
      (node (ref "U1") (pin "44") (pinfunction "ADDR2_44") (pintype "passive"))
      (node (ref "U1") (pin "48") (pinfunction "GND_48") (pintype "passive"))
      (node (ref "U1") (pin "49") (pinfunction "GND_49") (pintype "passive"))
      (node (ref "U1") (pin "5") (pinfunction "PGND_5") (pintype "passive"))
      (node (ref "U2") (pin "12") (pinfunction "PGND_12") (pintype "passive"))
      (node (ref "U2") (pin "34") (pinfunction "AGND_34") (pintype "passive"))
      (node (ref "U2") (pin "44") (pinfunction "ADDR2_44") (pintype "passive"))
      (node (ref "U2") (pin "48") (pinfunction "GND_48") (pintype "passive"))
      (node (ref "U2") (pin "49") (pinfunction "GND_49") (pintype "passive"))
      (node (ref "U2") (pin "5") (pinfunction "PGND_5") (pintype "passive"))
    )
    (net (code "54") (name "Net-(U1-IICRST)") (class "Default")
      (node (ref "R3") (pin "1") (pintype "passive"))
      (node (ref "U1") (pin "47") (pinfunction "IICRST_47") (pintype "passive"))
    )
    (net (code "55") (name "Net-(U1-RSET)") (class "Default")
      (node (ref "R4") (pin "1") (pintype "passive"))
      (node (ref "U1") (pin "35") (pinfunction "RSET_35") (pintype "passive"))
    )
    (net (code "56") (name "Net-(U1-SDB)") (class "Default")
      (node (ref "R2") (pin "1") (pintype "passive"))
      (node (ref "U1") (pin "46") (pinfunction "SDB_46") (pintype "passive"))
    )
    (net (code "57") (name "Net-(U2-IICRST)") (class "Default")
      (node (ref "R6") (pin "1") (pintype "passive"))
      (node (ref "U2") (pin "47") (pinfunction "IICRST_47") (pintype "passive"))
    )
    (net (code "58") (name "Net-(U2-RSET)") (class "Default")
      (node (ref "R7") (pin "1") (pintype "passive"))
      (node (ref "U2") (pin "35") (pinfunction "RSET_35") (pintype "passive"))
    )
    (net (code "59") (name "Net-(U2-SDB)") (class "Default")
      (node (ref "R5") (pin "1") (pintype "passive"))
      (node (ref "U2") (pin "46") (pinfunction "SDB_46") (pintype "passive"))
    )
    (net (code "60") (name "unconnected-(U1-INTB-Pad45)") (class "Default")
      (node (ref "U1") (pin "45") (pinfunction "INTB_45") (pintype "passive+no_connect"))
    )
    (net (code "61") (name "unconnected-(U1-SW10-Pad13)") (class "Default")
      (node (ref "U1") (pin "13") (pinfunction "SW10_13") (pintype "passive+no_connect"))
    )
    (net (code "62") (name "unconnected-(U1-SW11-Pad14)") (class "Default")
      (node (ref "U1") (pin "14") (pinfunction "SW11_14") (pintype "passive+no_connect"))
    )
    (net (code "63") (name "unconnected-(U1-SW12-Pad15)") (class "Default")
      (node (ref "U1") (pin "15") (pinfunction "SW12_15") (pintype "passive+no_connect"))
    )
    (net (code "64") (name "unconnected-(U2-CS15-Pad32)") (class "Default")
      (node (ref "U2") (pin "32") (pinfunction "CS15_32") (pintype "passive+no_connect"))
    )
    (net (code "65") (name "unconnected-(U2-CS16-Pad33)") (class "Default")
      (node (ref "U2") (pin "33") (pinfunction "CS16_33") (pintype "passive+no_connect"))
    )
    (net (code "66") (name "unconnected-(U2-INTB-Pad45)") (class "Default")
      (node (ref "U2") (pin "45") (pinfunction "INTB_45") (pintype "passive+no_connect"))
    )
    (net (code "67") (name "unconnected-(U2-SW10-Pad13)") (class "Default")
      (node (ref "U2") (pin "13") (pinfunction "SW10_13") (pintype "passive+no_connect"))
    )
    (net (code "68") (name "unconnected-(U2-SW11-Pad14)") (class "Default")
      (node (ref "U2") (pin "14") (pinfunction "SW11_14") (pintype "passive+no_connect"))
    )
    (net (code "69") (name "unconnected-(U2-SW12-Pad15)") (class "Default")
      (node (ref "U2") (pin "15") (pinfunction "SW12_15") (pintype "passive+no_connect"))
    )
  )
)
